# 780-00038_rev2_Pg1_SCH_Flex_Pwr_Sply.net
KiCad netlist of a schematic drawn in Altium Designer
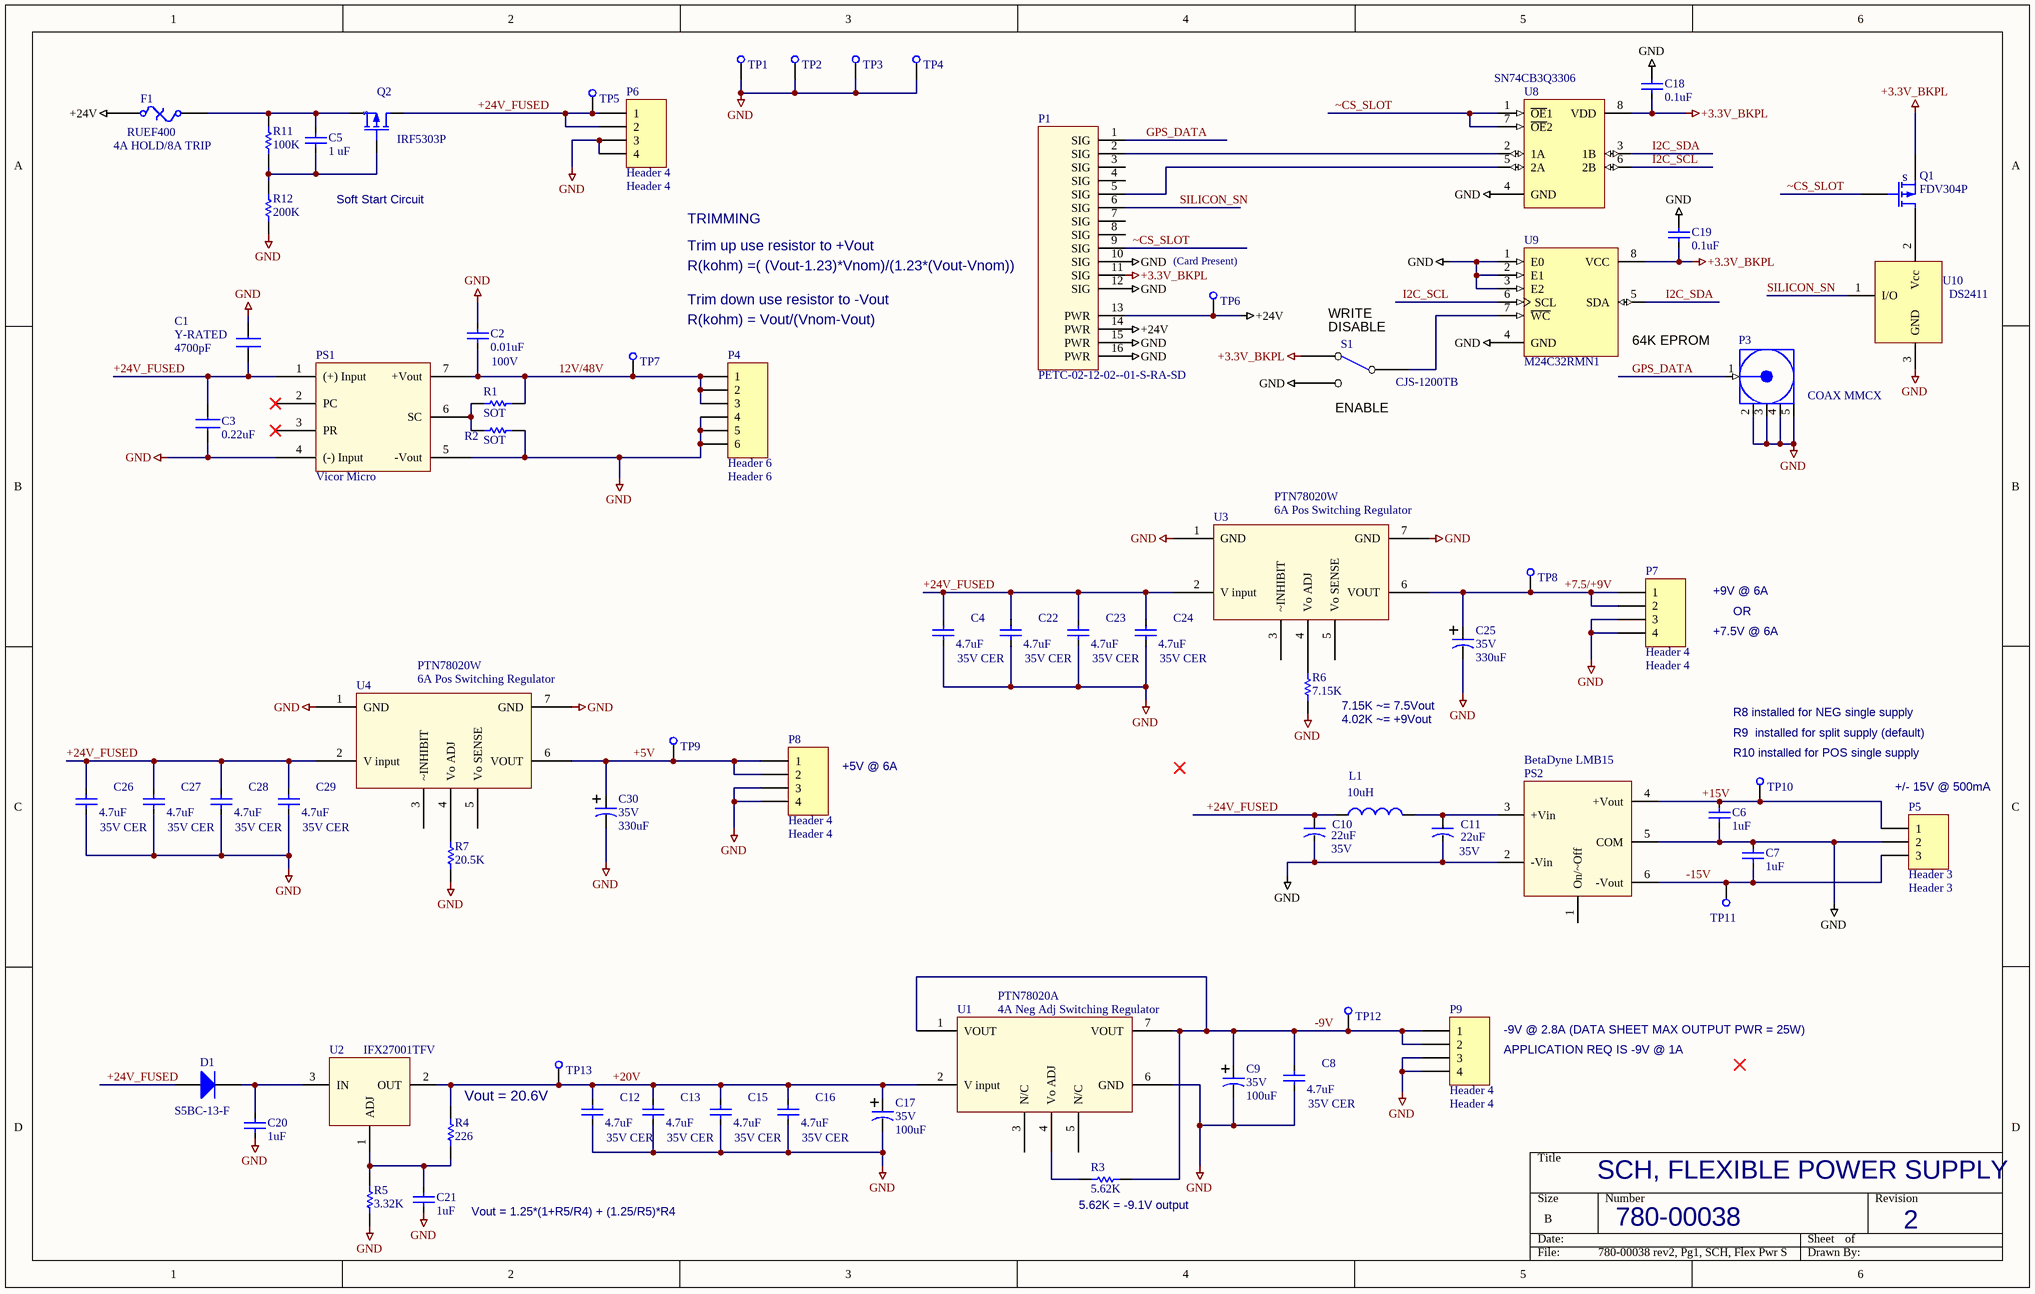
[diagram p0: 780-00038 rev2, Pg1, SCH, Flex Pwr Sply.SchDoc]

(export (version "E")
  (design (tool "Eeschema 10.0.6"))
  (components
    (comp (ref "C1")
      (value "Y-RATED")
      (footprint "1812")
      (fields (field (name "MANUFACTURER") "Murata") (field (name "ALTIUM_VALUE") "4700pF"))
      (libsource (lib "JON_1_Library") (part "CAP NP_DOUG"))
    )
    (comp (ref "C2")
      (value "100V")
      (footprint "SMD_0805")
      (description "Capacitor")
      (fields (field (name "MANUFACTURER") "Johanson") (field (name "ALTIUM_VALUE") "0.01uF"))
      (libsource (lib "Richs Schematic Components") (part "Cap SMD"))
    )
    (comp (ref "C3")
      (value "0.22uF")
      (footprint "1812")
      (fields (field (name "MANUFACTURER") "TDK"))
      (libsource (lib "JON_1_Library") (part "CAP NP_DOUG"))
    )
    (comp (ref "C4")
      (value "35V CER")
      (footprint "SMD_0805")
      (description "Capacitor")
      (fields (field (name "ALTIUM_VALUE") "4.7uF"))
      (libsource (lib "Richs Schematic Components") (part "Cap SMD"))
    )
    (comp (ref "C5")
      (value "1 uF")
      (footprint "SMD_0805")
      (description "Capacitor")
      (fields (field (name "Comment") "Cap SMD"))
      (libsource (lib "Richs Schematic Components") (part "Cap SMD"))
    )
    (comp (ref "C6")
      (value "1uF")
      (footprint "SMD_0805")
      (description "Capacitor")
      (fields (field (name "Comment") "Cap SMD"))
      (libsource (lib "Richs Schematic Components") (part "Cap SMD"))
    )
    (comp (ref "C7")
      (value "1uF")
      (footprint "SMD_0805")
      (description "Capacitor")
      (fields (field (name "Comment") "Cap SMD"))
      (libsource (lib "Richs Schematic Components") (part "Cap SMD"))
    )
    (comp (ref "C8")
      (value "35V CER")
      (footprint "SMD_0805")
      (description "Capacitor")
      (fields (field (name "ALTIUM_VALUE") "4.7uF"))
      (libsource (lib "Richs Schematic Components") (part "Cap SMD"))
    )
    (comp (ref "C9")
      (value "35V")
      (footprint "CAP, Thru Hole 8mm dia")
      (description "Radial Thru hole")
      (fields (field (name "ALTIUM_VALUE") "100uF"))
      (libsource (lib "Richs Schematic Components") (part "Cap Elec, 100 uF, 35V"))
    )
    (comp (ref "C10")
      (value "35V")
      (footprint "SMD_CAP_7343")
      (description "outline 6.0mm x 3.2mm")
      (fields (field (name "MANUFACTURER") "Kemet") (field (name "ALTIUM_VALUE") "22uF"))
      (libsource (lib "Richs Schematic Components") (part "Cap Tant 35V"))
    )
    (comp (ref "C11")
      (value "35V")
      (footprint "SMD_CAP_7343")
      (description "outline 6.0mm x 3.2mm")
      (fields (field (name "MANUFACTURER") "Kemet") (field (name "ALTIUM_VALUE") "22uF"))
      (libsource (lib "Richs Schematic Components") (part "Cap Tant 35V"))
    )
    (comp (ref "C12")
      (value "35V CER")
      (footprint "SMD_0805")
      (description "Capacitor")
      (fields (field (name "ALTIUM_VALUE") "4.7uF"))
      (libsource (lib "Richs Schematic Components") (part "Cap SMD"))
    )
    (comp (ref "C13")
      (value "35V CER")
      (footprint "SMD_0805")
      (description "Capacitor")
      (fields (field (name "ALTIUM_VALUE") "4.7uF"))
      (libsource (lib "Richs Schematic Components") (part "Cap SMD"))
    )
    (comp (ref "C15")
      (value "35V CER")
      (footprint "SMD_0805")
      (description "Capacitor")
      (fields (field (name "ALTIUM_VALUE") "4.7uF"))
      (libsource (lib "Richs Schematic Components") (part "Cap SMD"))
    )
    (comp (ref "C16")
      (value "35V CER")
      (footprint "SMD_0805")
      (description "Capacitor")
      (fields (field (name "ALTIUM_VALUE") "4.7uF"))
      (libsource (lib "Richs Schematic Components") (part "Cap SMD"))
    )
    (comp (ref "C17")
      (value "35V")
      (footprint "CAP, Thru Hole 8mm dia")
      (description "Radial Thru hole")
      (fields (field (name "ALTIUM_VALUE") "100uF"))
      (libsource (lib "Richs Schematic Components") (part "Cap Elec, 100 uF, 35V"))
    )
    (comp (ref "C18")
      (value "0.1uF")
      (footprint "SMD_0805")
      (description "Capacitor")
      (fields (field (name "MANUFACTURER") "AVX") (field (name "Comment") "Cap SMD"))
      (libsource (lib "Richs Schematic Components") (part "Cap SMD"))
    )
    (comp (ref "C19")
      (value "0.1uF")
      (footprint "SMD_0805")
      (description "Capacitor")
      (fields (field (name "MANUFACTURER") "AVX") (field (name "Comment") "Cap SMD"))
      (libsource (lib "Richs Schematic Components") (part "Cap SMD"))
    )
    (comp (ref "C20")
      (value "1uF")
      (footprint "SMD_0805")
      (description "Capacitor")
      (fields (field (name "Comment") "Cap SMD"))
      (libsource (lib "Richs Schematic Components") (part "Cap SMD"))
    )
    (comp (ref "C21")
      (value "1uF")
      (footprint "SMD_0805")
      (description "Capacitor")
      (fields (field (name "Comment") "Cap SMD"))
      (libsource (lib "Richs Schematic Components") (part "Cap SMD"))
    )
    (comp (ref "C22")
      (value "35V CER")
      (footprint "SMD_0805")
      (description "Capacitor")
      (fields (field (name "ALTIUM_VALUE") "4.7uF"))
      (libsource (lib "Richs Schematic Components") (part "Cap SMD"))
    )
    (comp (ref "C23")
      (value "35V CER")
      (footprint "SMD_0805")
      (description "Capacitor")
      (fields (field (name "ALTIUM_VALUE") "4.7uF"))
      (libsource (lib "Richs Schematic Components") (part "Cap SMD"))
    )
    (comp (ref "C24")
      (value "35V CER")
      (footprint "SMD_0805")
      (description "Capacitor")
      (fields (field (name "ALTIUM_VALUE") "4.7uF"))
      (libsource (lib "Richs Schematic Components") (part "Cap SMD"))
    )
    (comp (ref "C25")
      (value "35V")
      (footprint "CAP, Thru Hole 10mm dia")
      (description "Radial Thru hole")
      (fields (field (name "ALTIUM_VALUE") "330uF"))
      (libsource (lib "Richs Schematic Components") (part "Cap Elec, 330 uF, 35V"))
    )
    (comp (ref "C26")
      (value "35V CER")
      (footprint "SMD_0805")
      (description "Capacitor")
      (fields (field (name "ALTIUM_VALUE") "4.7uF"))
      (libsource (lib "Richs Schematic Components") (part "Cap SMD"))
    )
    (comp (ref "C27")
      (value "35V CER")
      (footprint "SMD_0805")
      (description "Capacitor")
      (fields (field (name "ALTIUM_VALUE") "4.7uF"))
      (libsource (lib "Richs Schematic Components") (part "Cap SMD"))
    )
    (comp (ref "C28")
      (value "35V CER")
      (footprint "SMD_0805")
      (description "Capacitor")
      (fields (field (name "ALTIUM_VALUE") "4.7uF"))
      (libsource (lib "Richs Schematic Components") (part "Cap SMD"))
    )
    (comp (ref "C29")
      (value "35V CER")
      (footprint "SMD_0805")
      (description "Capacitor")
      (fields (field (name "ALTIUM_VALUE") "4.7uF"))
      (libsource (lib "Richs Schematic Components") (part "Cap SMD"))
    )
    (comp (ref "C30")
      (value "35V")
      (footprint "CAP, Thru Hole 10mm dia")
      (description "Radial Thru hole")
      (fields (field (name "ALTIUM_VALUE") "330uF"))
      (libsource (lib "Richs Schematic Components") (part "Cap Elec, 330 uF, 35V"))
    )
    (comp (ref "D1")
      (value "S5BC-13-F")
      (footprint "SMC")
      (description "RECTIFIER GPP SMD 100V 5A SMC")
      (fields (field (name "MANUFACTURER") "Diodes Inc"))
      (libsource (lib "Miscellaneous Devices") (part "Diode"))
    )
    (comp (ref "F1")
      (value "RUEF400")
      (footprint "PolySwitch Radial 0.2")
      (description "PolySwitch RUE Series")
      (fields
        (field (name "MANUFACTURER") "Tyco Electronics")
        (field (name "ALTIUM_VALUE") "4A HOLD/8A TRIP")
      )
      (libsource (lib "Richs Schematic Components") (part "Fuse Thermal"))
    )
    (comp (ref "L1")
      (value "10uH")
      (footprint "Inductor TDC SLF")
      (description "Inductor")
      (fields (field (name "MANUFACTURER") "TDK") (field (name "Comment") "445-3869-1-ND"))
      (libsource (lib "Richs Schematic Components") (part "Inductor SMD 10uH 1.8A"))
    )
    (comp (ref "P1")
      (value "PETC-02-12-02--01-S-RA-SD")
      (footprint "PETC-02-12-02-01-RA")
      (description "SAMTEC, SIGNAL(12)+PWR(4)")
      (fields (field (name "MANUFACTURER") "SAMTEC"))
      (libsource (lib "Richs Schematic Components") (part "PETC-02-12-02--01-S-RA-SD"))
    )
    (comp (ref "P3")
      (value "COAX MMCX")
      (footprint "Miscellaneous Connectors:MMCX2.54-V5")
      (description "RF Coaxial PCB Connector, MMCX; Thru-Hole, Vertical Mount Plug,  50 Ohm Impedance")
      (fields (field (name "MANUFACTURER") "Emerson"))
      (libsource (lib "Richs Schematic Components") (part "COAX-M"))
    )
    (comp (ref "P4")
      (value "Header 6")
      (footprint "HDR1X6 for IDC")
      (description "Header, 6-Pin")
      (fields (field (name "ALTIUM_VALUE") "Header 6"))
      (libsource (lib "Richs Schematic Components") (part "Header 6"))
    )
    (comp (ref "P5")
      (value "Header 3")
      (footprint "HDR1X3 for IDC")
      (description "Header, 4-Pin")
      (fields (field (name "ALTIUM_VALUE") "Header 3"))
      (libsource (lib "Richs Schematic Components") (part "Header 3, MTA100"))
    )
    (comp (ref "P6")
      (value "Header 4")
      (footprint "HDR1X4 for IDC")
      (description "Header, 4-Pin")
      (fields (field (name "ALTIUM_VALUE") "Header 4"))
      (libsource (lib "Richs Schematic Components") (part "Header 4"))
    )
    (comp (ref "P7")
      (value "Header 4")
      (footprint "HDR1X4 for IDC")
      (description "Header, 4-Pin")
      (fields (field (name "ALTIUM_VALUE") "Header 4"))
      (libsource (lib "Richs Schematic Components") (part "Header 4"))
    )
    (comp (ref "P8")
      (value "Header 4")
      (footprint "HDR1X4 for IDC")
      (description "Header, 4-Pin")
      (fields (field (name "ALTIUM_VALUE") "Header 4"))
      (libsource (lib "Richs Schematic Components") (part "Header 4"))
    )
    (comp (ref "P9")
      (value "Header 4")
      (footprint "HDR1X4 for IDC")
      (description "Header, 4-Pin")
      (fields (field (name "ALTIUM_VALUE") "Header 4"))
      (libsource (lib "Richs Schematic Components") (part "Header 4"))
    )
    (comp (ref "PS1")
      (value "Vicor Micro")
      (footprint "Vicor Micro SurfMate")
      (libsource (lib "Richs Schematic Components") (part "Vicor Micro"))
    )
    (comp (ref "PS2")
      (value "BetaDyne LMB15")
      (footprint "BetaDyne LNB15, DC/DC")
      (description "DC/DC LMB15 15W, Dual Output")
      (libsource (lib "Richs Schematic Components") (part "BetaDyne LMB15"))
    )
    (comp (ref "Q1")
      (value "FDV304P")
      (footprint "SMD_SOT23_3")
      (description "P-MOSFET LOGIC LEVEL")
      (fields (field (name "MANUFACTURER") "Fairchild"))
      (libsource (lib "Richs Schematic Components") (part "FDV304P"))
    )
    (comp (ref "Q2")
      (value "IRF5303P")
      (footprint "TO-252(D-PAK)  PowerPAD")
      (description "P-Chan MOSFET")
      (fields (field (name "MANUFACTURER") "INT'l Rectifier"))
      (libsource (lib "Richs Schematic Components") (part "IRF5303P"))
    )
    (comp (ref "R1")
      (value "SOT")
      (footprint "SMD_0805")
      (description "Resistor 0805")
      (fields (field (name "MANUFACTURER") "Vishay/Dale") (field (name "Comment") "Res 0805"))
      (libsource (lib "Richs Schematic Components") (part "Res SMD"))
    )
    (comp (ref "R2")
      (value "SOT")
      (footprint "SMD_0805")
      (description "Resistor 0805")
      (fields (field (name "MANUFACTURER") "Vishay/Dale") (field (name "Comment") "Res 0805"))
      (libsource (lib "Richs Schematic Components") (part "Res SMD"))
    )
    (comp (ref "R3")
      (value "5.62K")
      (footprint "SMD_0805")
      (description "Resistor 0805")
      (fields (field (name "MANUFACTURER") "Vishay/Dale") (field (name "Comment") "Res 0805"))
      (libsource (lib "Richs Schematic Components") (part "Res SMD"))
    )
    (comp (ref "R4")
      (value "226")
      (footprint "SMD_0805")
      (description "Resistor 0805")
      (fields (field (name "MANUFACTURER") "Vishay/Dale") (field (name "Comment") "Res 0805"))
      (libsource (lib "Richs Schematic Components") (part "Res SMD"))
    )
    (comp (ref "R5")
      (value "3.32K")
      (footprint "SMD_0805")
      (description "Resistor 0805")
      (fields (field (name "MANUFACTURER") "Vishay/Dale") (field (name "Comment") "Res 0805"))
      (libsource (lib "Richs Schematic Components") (part "Res SMD"))
    )
    (comp (ref "R6")
      (value "7.15K")
      (footprint "SMD_0805")
      (description "Resistor 0805")
      (fields (field (name "MANUFACTURER") "Vishay/Dale") (field (name "Comment") "Res 0805"))
      (libsource (lib "Richs Schematic Components") (part "Res SMD"))
    )
    (comp (ref "R7")
      (value "20.5K")
      (footprint "SMD_0805")
      (description "Resistor 0805")
      (fields (field (name "MANUFACTURER") "Vishay/Dale") (field (name "Comment") "Res 0805"))
      (libsource (lib "Richs Schematic Components") (part "Res SMD"))
    )
    (comp (ref "R11")
      (value "100K")
      (footprint "SMD_0805")
      (description "Resistor 0805")
      (fields (field (name "MANUFACTURER") "Vishay/Dale") (field (name "Comment") "Res 0805"))
      (libsource (lib "Richs Schematic Components") (part "Res SMD"))
    )
    (comp (ref "R12")
      (value "200K")
      (footprint "SMD_0805")
      (description "Resistor 0805")
      (fields (field (name "MANUFACTURER") "Vishay/Dale") (field (name "Comment") "Res 0805"))
      (libsource (lib "Richs Schematic Components") (part "Res SMD"))
    )
    (comp (ref "S1")
      (value "CJS-1200TB")
      (footprint "CAS-120B")
      (fields (field (name "MANUFACTURER") "Copal Electronics"))
      (libsource (lib "JON_1_Library") (part "SW_SPDT_DOUG"))
    )
    (comp (ref "TP1")
      (value "Test point")
      (footprint "Protel 99SE BANKS PCB:PAD_80D_052H")
      (description "Test Point")
      (fields (field (name "MANUFACTURER") "Keystone"))
      (libsource (lib "Richs Schematic Components") (part "Test point"))
    )
    (comp (ref "TP2")
      (value "Test point")
      (footprint "Protel 99SE BANKS PCB:PAD_80D_052H")
      (description "Test Point")
      (fields (field (name "MANUFACTURER") "Keystone"))
      (libsource (lib "Richs Schematic Components") (part "Test point"))
    )
    (comp (ref "TP3")
      (value "Test point")
      (footprint "Protel 99SE BANKS PCB:PAD_80D_052H")
      (description "Test Point")
      (fields (field (name "MANUFACTURER") "Keystone"))
      (libsource (lib "Richs Schematic Components") (part "Test point"))
    )
    (comp (ref "TP4")
      (value "Test point")
      (footprint "Protel 99SE BANKS PCB:PAD_80D_052H")
      (description "Test Point")
      (fields (field (name "MANUFACTURER") "Keystone"))
      (libsource (lib "Richs Schematic Components") (part "Test point"))
    )
    (comp (ref "TP5")
      (value "Test point")
      (footprint "Protel 99SE BANKS PCB:PAD_80D_052H")
      (description "Test Point")
      (fields (field (name "MANUFACTURER") "Keystone"))
      (libsource (lib "Richs Schematic Components") (part "Test point"))
    )
    (comp (ref "TP6")
      (value "Test point")
      (footprint "Protel 99SE BANKS PCB:PAD_80D_052H")
      (description "Test Point")
      (fields (field (name "MANUFACTURER") "Keystone"))
      (libsource (lib "Richs Schematic Components") (part "Test point"))
    )
    (comp (ref "TP7")
      (value "Test point")
      (footprint "Protel 99SE BANKS PCB:PAD_80D_052H")
      (description "Test Point")
      (fields (field (name "MANUFACTURER") "Keystone"))
      (libsource (lib "Richs Schematic Components") (part "Test point"))
    )
    (comp (ref "TP8")
      (value "Test point")
      (footprint "Protel 99SE BANKS PCB:PAD_80D_052H")
      (description "Test Point")
      (fields (field (name "MANUFACTURER") "Keystone"))
      (libsource (lib "Richs Schematic Components") (part "Test point"))
    )
    (comp (ref "TP9")
      (value "Test point")
      (footprint "Protel 99SE BANKS PCB:PAD_80D_052H")
      (description "Test Point")
      (fields (field (name "MANUFACTURER") "Keystone"))
      (libsource (lib "Richs Schematic Components") (part "Test point"))
    )
    (comp (ref "TP10")
      (value "Test point")
      (footprint "Protel 99SE BANKS PCB:PAD_80D_052H")
      (description "Test Point")
      (fields (field (name "MANUFACTURER") "Keystone"))
      (libsource (lib "Richs Schematic Components") (part "Test point"))
    )
    (comp (ref "TP11")
      (value "Test point")
      (footprint "Protel 99SE BANKS PCB:PAD_80D_052H")
      (description "Test Point")
      (fields (field (name "MANUFACTURER") "Keystone"))
      (libsource (lib "Richs Schematic Components") (part "Test point"))
    )
    (comp (ref "TP12")
      (value "Test point")
      (footprint "Protel 99SE BANKS PCB:PAD_80D_052H")
      (description "Test Point")
      (fields (field (name "MANUFACTURER") "Keystone"))
      (libsource (lib "Richs Schematic Components") (part "Test point"))
    )
    (comp (ref "TP13")
      (value "Test point")
      (footprint "Protel 99SE BANKS PCB:PAD_80D_052H")
      (description "Test Point")
      (fields (field (name "MANUFACTURER") "Keystone"))
      (libsource (lib "Richs Schematic Components") (part "Test point"))
    )
    (comp (ref "U1")
      (value "4A Neg Adj Switching Regulator")
      (footprint "TEXAS Inst Switching Regulator")
      (description "Neg Adj Switching Regulator")
      (fields (field (name "ALTIUM_VALUE") "PTN78020A"))
      (libsource (lib "Richs Schematic Components") (part "PTN78020A"))
    )
    (comp (ref "U2")
      (value "IFX27001TFV")
      (footprint "TO-252(D-PAK)  PowerPAD")
      (description "IFX27001")
      (fields (field (name "MANUFACTURER") "Infineon") (field (name "Comment") "Voltage Reg, Adj"))
      (libsource (lib "Richs Schematic Components") (part "Voltage Reg, Adjustable"))
    )
    (comp (ref "U3")
      (value "6A Pos Switching Regulator")
      (footprint "TEXAS Inst Switching Regulator")
      (description "Pos Adj Switching Regulator")
      (fields (field (name "ALTIUM_VALUE") "PTN78020W"))
      (libsource (lib "Richs Schematic Components") (part "PTN78020W"))
    )
    (comp (ref "U4")
      (value "6A Pos Switching Regulator")
      (footprint "TEXAS Inst Switching Regulator")
      (description "Pos Adj Switching Regulator")
      (fields (field (name "ALTIUM_VALUE") "PTN78020W"))
      (libsource (lib "Richs Schematic Components") (part "PTN78020W"))
    )
    (comp (ref "U8")
      (value "SN74CB3Q3306")
      (footprint "PW008_N")
      (description "Dual FET Bus Switch")
      (fields (field (name "MANUFACTURER") "TI") (field (name "Comment") "SN74CBT3306PWLE"))
      (libsource (lib "TI Logic Switch") (part "SN74CBT3306PWLE"))
    )
    (comp (ref "U9")
      (value "M24C32RMN1")
      (footprint "SOP8_N")
      (description "32 Kbit Serial I²C Bus EEPROM")
      (libsource (lib "ST Memory EEPROM Serial") (part "M24C32RMN1"))
    )
    (comp (ref "U10")
      (value "DS2411")
      (footprint "SMD_SOT23_3")
      (description "Silicon Serial Number")
      (fields (field (name "MANUFACTURER") "Dallas"))
      (libsource (lib "Richs Schematic Components") (part "DS2411"))
    )
  )
  (nets
    (net (code "1") (name "+3.3V_BKPL") (class "Default")
      (node (ref "C18") (pin "1") (pinfunction "1_1") (pintype "passive"))
      (node (ref "C19") (pin "1") (pinfunction "1_1") (pintype "passive"))
      (node (ref "P1") (pin "11") (pinfunction "SIG_11") (pintype "passive"))
      (node (ref "Q1") (pin "2") (pinfunction "S_2") (pintype "passive"))
      (node (ref "S1") (pin "3") (pinfunction "NC_3") (pintype "passive"))
      (node (ref "U8") (pin "8") (pinfunction "VDD_8") (pintype "power_in"))
      (node (ref "U9") (pin "8") (pinfunction "VCC_8") (pintype "power_in"))
    )
    (net (code "2") (name "+24V") (class "Default")
      (node (ref "F1") (pin "1") (pinfunction "1_1") (pintype "passive"))
      (node (ref "P1") (pin "13") (pinfunction "PWR_13") (pintype "passive"))
      (node (ref "P1") (pin "14") (pinfunction "PWR_14") (pintype "passive"))
      (node (ref "TP6") (pin "1") (pinfunction "TP_1") (pintype "passive"))
    )
    (net (code "3") (name "/+5V") (class "Default")
      (node (ref "C30") (pin "1") (pinfunction "1_1") (pintype "passive"))
      (node (ref "P8") (pin "1") (pinfunction "1_1") (pintype "passive"))
      (node (ref "P8") (pin "2") (pinfunction "2_2") (pintype "passive"))
      (node (ref "TP9") (pin "1") (pinfunction "TP_1") (pintype "passive"))
      (node (ref "U4") (pin "6") (pinfunction "VOUT_6") (pintype "passive"))
    )
    (net (code "4") (name "/+7.5{slash}+9V") (class "Default")
      (node (ref "C25") (pin "1") (pinfunction "1_1") (pintype "passive"))
      (node (ref "P7") (pin "1") (pinfunction "1_1") (pintype "passive"))
      (node (ref "P7") (pin "2") (pinfunction "2_2") (pintype "passive"))
      (node (ref "TP8") (pin "1") (pinfunction "TP_1") (pintype "passive"))
      (node (ref "U3") (pin "6") (pinfunction "VOUT_6") (pintype "passive"))
    )
    (net (code "5") (name "/+15V") (class "Default")
      (node (ref "C6") (pin "2") (pinfunction "2_2") (pintype "passive"))
      (node (ref "P5") (pin "1") (pinfunction "1_1") (pintype "passive"))
      (node (ref "PS2") (pin "4") (pinfunction "+Vout_4") (pintype "passive"))
      (node (ref "TP10") (pin "1") (pinfunction "TP_1") (pintype "passive"))
    )
    (net (code "6") (name "/+20V") (class "Default")
      (node (ref "C12") (pin "2") (pinfunction "2_2") (pintype "passive"))
      (node (ref "C13") (pin "2") (pinfunction "2_2") (pintype "passive"))
      (node (ref "C15") (pin "2") (pinfunction "2_2") (pintype "passive"))
      (node (ref "C16") (pin "2") (pinfunction "2_2") (pintype "passive"))
      (node (ref "C17") (pin "1") (pinfunction "1_1") (pintype "passive"))
      (node (ref "R4") (pin "2") (pinfunction "2_2") (pintype "passive"))
      (node (ref "TP13") (pin "1") (pinfunction "TP_1") (pintype "passive"))
      (node (ref "U1") (pin "2") (pinfunction "V_input_2") (pintype "passive"))
      (node (ref "U2") (pin "2") (pinfunction "OUT_2") (pintype "passive"))
    )
    (net (code "7") (name "/+24V_FUSED") (class "Default")
      (node (ref "C1") (pin "2") (pinfunction "2_2") (pintype "passive"))
      (node (ref "C10") (pin "pos") (pinfunction "1_pos") (pintype "passive"))
      (node (ref "C22") (pin "2") (pinfunction "2_2") (pintype "passive"))
      (node (ref "C23") (pin "2") (pinfunction "2_2") (pintype "passive"))
      (node (ref "C24") (pin "2") (pinfunction "2_2") (pintype "passive"))
      (node (ref "C26") (pin "2") (pinfunction "2_2") (pintype "passive"))
      (node (ref "C27") (pin "2") (pinfunction "2_2") (pintype "passive"))
      (node (ref "C28") (pin "2") (pinfunction "2_2") (pintype "passive"))
      (node (ref "C29") (pin "2") (pinfunction "2_2") (pintype "passive"))
      (node (ref "C3") (pin "2") (pinfunction "2_2") (pintype "passive"))
      (node (ref "C4") (pin "2") (pinfunction "2_2") (pintype "passive"))
      (node (ref "D1") (pin "1") (pinfunction "A_1") (pintype "passive"))
      (node (ref "L1") (pin "1") (pinfunction "1_1") (pintype "passive"))
      (node (ref "P6") (pin "1") (pinfunction "1_1") (pintype "passive"))
      (node (ref "P6") (pin "2") (pinfunction "2_2") (pintype "passive"))
      (node (ref "PS1") (pin "1") (pinfunction "(+)_Input_1") (pintype "passive"))
      (node (ref "Q2") (pin "2") (pinfunction "D_2") (pintype "passive"))
      (node (ref "TP5") (pin "1") (pinfunction "TP_1") (pintype "passive"))
      (node (ref "U3") (pin "2") (pinfunction "V_input_2") (pintype "passive"))
      (node (ref "U4") (pin "2") (pinfunction "V_input_2") (pintype "passive"))
    )
    (net (code "8") (name "/-9V") (class "Default")
      (node (ref "C8") (pin "2") (pinfunction "2_2") (pintype "passive"))
      (node (ref "C9") (pin "1") (pinfunction "1_1") (pintype "passive"))
      (node (ref "P9") (pin "1") (pinfunction "1_1") (pintype "passive"))
      (node (ref "P9") (pin "2") (pinfunction "2_2") (pintype "passive"))
      (node (ref "R3") (pin "2") (pinfunction "2_2") (pintype "passive"))
      (node (ref "TP12") (pin "1") (pinfunction "TP_1") (pintype "passive"))
      (node (ref "U1") (pin "1") (pinfunction "VOUT_1") (pintype "passive"))
      (node (ref "U1") (pin "7") (pinfunction "VOUT_7") (pintype "passive"))
    )
    (net (code "9") (name "/-15V") (class "Default")
      (node (ref "C7") (pin "1") (pinfunction "1_1") (pintype "passive"))
      (node (ref "P5") (pin "3") (pinfunction "3_3") (pintype "passive"))
      (node (ref "PS2") (pin "6") (pinfunction "-Vout_6") (pintype "passive"))
      (node (ref "TP11") (pin "1") (pinfunction "TP_1") (pintype "passive"))
    )
    (net (code "10") (name "/12V{slash}48V") (class "Default")
      (node (ref "C2") (pin "1") (pinfunction "1_1") (pintype "passive"))
      (node (ref "P4") (pin "1") (pinfunction "1_1") (pintype "passive"))
      (node (ref "P4") (pin "2") (pinfunction "2_2") (pintype "passive"))
      (node (ref "P4") (pin "3") (pinfunction "3_3") (pintype "passive"))
      (node (ref "PS1") (pin "7") (pinfunction "+Vout_7") (pintype "passive"))
      (node (ref "R1") (pin "2") (pinfunction "2_2") (pintype "passive"))
      (node (ref "TP7") (pin "1") (pinfunction "TP_1") (pintype "passive"))
    )
    (net (code "11") (name "/GPS_DATA") (class "Default")
      (node (ref "P1") (pin "1") (pinfunction "SIG_1") (pintype "passive"))
      (node (ref "P3") (pin "1") (pinfunction "Signal_1") (pintype "input"))
    )
    (net (code "12") (name "/I2C_SCL") (class "Default")
      (node (ref "U8") (pin "6") (pinfunction "2B_6") (pintype "bidirectional"))
      (node (ref "U9") (pin "6") (pinfunction "SCL_6") (pintype "input"))
    )
    (net (code "13") (name "/I2C_SDA") (class "Default")
      (node (ref "U8") (pin "3") (pinfunction "1B_3") (pintype "bidirectional"))
      (node (ref "U9") (pin "5") (pinfunction "SDA_5") (pintype "bidirectional"))
    )
    (net (code "14") (name "/SILICON_SN") (class "Default")
      (node (ref "P1") (pin "6") (pinfunction "SIG_6") (pintype "passive"))
      (node (ref "U10") (pin "1") (pinfunction "I/O_1") (pintype "passive"))
    )
    (net (code "15") (name "/~CS_SLOT") (class "Default")
      (node (ref "P1") (pin "9") (pinfunction "SIG_9") (pintype "passive"))
      (node (ref "Q1") (pin "1") (pinfunction "G_1") (pintype "passive"))
      (node (ref "U8") (pin "1") (pinfunction "~{OE}1_1") (pintype "input"))
      (node (ref "U8") (pin "7") (pinfunction "~{OE}2_7") (pintype "input"))
    )
    (net (code "16") (name "GND") (class "Default")
      (node (ref "C1") (pin "1") (pinfunction "1_1") (pintype "passive"))
      (node (ref "C10") (pin "neg") (pinfunction "2_neg") (pintype "passive"))
      (node (ref "C11") (pin "neg") (pinfunction "2_neg") (pintype "passive"))
      (node (ref "C12") (pin "1") (pinfunction "1_1") (pintype "passive"))
      (node (ref "C13") (pin "1") (pinfunction "1_1") (pintype "passive"))
      (node (ref "C15") (pin "1") (pinfunction "1_1") (pintype "passive"))
      (node (ref "C16") (pin "1") (pinfunction "1_1") (pintype "passive"))
      (node (ref "C17") (pin "2") (pinfunction "2_2") (pintype "passive"))
      (node (ref "C18") (pin "2") (pinfunction "2_2") (pintype "passive"))
      (node (ref "C19") (pin "2") (pinfunction "2_2") (pintype "passive"))
      (node (ref "C2") (pin "2") (pinfunction "2_2") (pintype "passive"))
      (node (ref "C20") (pin "1") (pinfunction "1_1") (pintype "passive"))
      (node (ref "C21") (pin "1") (pinfunction "1_1") (pintype "passive"))
      (node (ref "C22") (pin "1") (pinfunction "1_1") (pintype "passive"))
      (node (ref "C23") (pin "1") (pinfunction "1_1") (pintype "passive"))
      (node (ref "C24") (pin "1") (pinfunction "1_1") (pintype "passive"))
      (node (ref "C25") (pin "2") (pinfunction "2_2") (pintype "passive"))
      (node (ref "C26") (pin "1") (pinfunction "1_1") (pintype "passive"))
      (node (ref "C27") (pin "1") (pinfunction "1_1") (pintype "passive"))
      (node (ref "C28") (pin "1") (pinfunction "1_1") (pintype "passive"))
      (node (ref "C29") (pin "1") (pinfunction "1_1") (pintype "passive"))
      (node (ref "C3") (pin "1") (pinfunction "1_1") (pintype "passive"))
      (node (ref "C30") (pin "2") (pinfunction "2_2") (pintype "passive"))
      (node (ref "C4") (pin "1") (pinfunction "1_1") (pintype "passive"))
      (node (ref "C6") (pin "1") (pinfunction "1_1") (pintype "passive"))
      (node (ref "C7") (pin "2") (pinfunction "2_2") (pintype "passive"))
      (node (ref "C8") (pin "1") (pinfunction "1_1") (pintype "passive"))
      (node (ref "C9") (pin "2") (pinfunction "2_2") (pintype "passive"))
      (node (ref "P1") (pin "10") (pinfunction "SIG_10") (pintype "passive"))
      (node (ref "P1") (pin "12") (pinfunction "SIG_12") (pintype "passive"))
      (node (ref "P1") (pin "15") (pinfunction "PWR_15") (pintype "passive"))
      (node (ref "P1") (pin "16") (pinfunction "PWR_16") (pintype "passive"))
      (node (ref "P3") (pin "2") (pinfunction "GND_2") (pintype "power_in"))
      (node (ref "P3") (pin "3") (pinfunction "GND_3") (pintype "power_in"))
      (node (ref "P3") (pin "4") (pinfunction "GND_4") (pintype "power_in"))
      (node (ref "P3") (pin "5") (pinfunction "GND_5") (pintype "power_in"))
      (node (ref "P4") (pin "4") (pinfunction "4_4") (pintype "passive"))
      (node (ref "P4") (pin "5") (pinfunction "5_5") (pintype "passive"))
      (node (ref "P4") (pin "6") (pinfunction "6_6") (pintype "passive"))
      (node (ref "P5") (pin "2") (pinfunction "2_2") (pintype "passive"))
      (node (ref "P6") (pin "3") (pinfunction "3_3") (pintype "passive"))
      (node (ref "P6") (pin "4") (pinfunction "4_4") (pintype "passive"))
      (node (ref "P7") (pin "3") (pinfunction "3_3") (pintype "passive"))
      (node (ref "P7") (pin "4") (pinfunction "4_4") (pintype "passive"))
      (node (ref "P8") (pin "3") (pinfunction "3_3") (pintype "passive"))
      (node (ref "P8") (pin "4") (pinfunction "4_4") (pintype "passive"))
      (node (ref "P9") (pin "3") (pinfunction "3_3") (pintype "passive"))
      (node (ref "P9") (pin "4") (pinfunction "4_4") (pintype "passive"))
      (node (ref "PS1") (pin "4") (pinfunction "(-)_Input_4") (pintype "passive"))
      (node (ref "PS1") (pin "5") (pinfunction "-Vout_5") (pintype "passive"))
      (node (ref "PS2") (pin "2") (pinfunction "-Vin_2") (pintype "passive"))
      (node (ref "PS2") (pin "5") (pinfunction "COM_5") (pintype "passive"))
      (node (ref "R12") (pin "1") (pinfunction "1_1") (pintype "passive"))
      (node (ref "R2") (pin "2") (pinfunction "2_2") (pintype "passive"))
      (node (ref "R5") (pin "1") (pinfunction "1_1") (pintype "passive"))
      (node (ref "R6") (pin "1") (pinfunction "1_1") (pintype "passive"))
      (node (ref "R7") (pin "1") (pinfunction "1_1") (pintype "passive"))
      (node (ref "S1") (pin "1") (pinfunction "NO_1") (pintype "passive"))
      (node (ref "TP1") (pin "1") (pinfunction "TP_1") (pintype "passive"))
      (node (ref "TP2") (pin "1") (pinfunction "TP_1") (pintype "passive"))
      (node (ref "TP3") (pin "1") (pinfunction "TP_1") (pintype "passive"))
      (node (ref "TP4") (pin "1") (pinfunction "TP_1") (pintype "passive"))
      (node (ref "U1") (pin "6") (pinfunction "GND_6") (pintype "passive"))
      (node (ref "U10") (pin "3") (pinfunction "GND_3") (pintype "passive"))
      (node (ref "U3") (pin "1") (pinfunction "GND_1") (pintype "passive"))
      (node (ref "U3") (pin "7") (pinfunction "GND_7") (pintype "passive"))
      (node (ref "U4") (pin "1") (pinfunction "GND_1") (pintype "passive"))
      (node (ref "U4") (pin "7") (pinfunction "GND_7") (pintype "passive"))
      (node (ref "U8") (pin "4") (pinfunction "GND_4") (pintype "power_in"))
      (node (ref "U9") (pin "1") (pinfunction "E0_1") (pintype "input"))
      (node (ref "U9") (pin "2") (pinfunction "E1_2") (pintype "input"))
      (node (ref "U9") (pin "3") (pinfunction "E2_3") (pintype "input"))
      (node (ref "U9") (pin "4") (pinfunction "GND_4") (pintype "power_in"))
    )
    (net (code "17") (name "Net-(C11-1)") (class "Default")
      (node (ref "C11") (pin "pos") (pinfunction "1_pos") (pintype "passive"))
      (node (ref "L1") (pin "2") (pinfunction "2_2") (pintype "passive"))
      (node (ref "PS2") (pin "3") (pinfunction "+Vin_3") (pintype "passive"))
    )
    (net (code "18") (name "Net-(D1-K)") (class "Default")
      (node (ref "C20") (pin "2") (pinfunction "2_2") (pintype "passive"))
      (node (ref "D1") (pin "2") (pinfunction "K_2") (pintype "passive"))
      (node (ref "U2") (pin "3") (pinfunction "IN_3") (pintype "passive"))
    )
    (net (code "19") (name "Net-(PS1-SC)") (class "Default")
      (node (ref "PS1") (pin "6") (pinfunction "SC_6") (pintype "passive"))
      (node (ref "R1") (pin "1") (pinfunction "1_1") (pintype "passive"))
      (node (ref "R2") (pin "1") (pinfunction "1_1") (pintype "passive"))
    )
    (net (code "20") (name "Net-(Q1-D)") (class "Default")
      (node (ref "Q1") (pin "3") (pinfunction "D_3") (pintype "passive"))
      (node (ref "U10") (pin "2") (pinfunction "Vcc_2") (pintype "passive"))
    )
    (net (code "21") (name "Net-(Q2-G)") (class "Default")
      (node (ref "C5") (pin "1") (pinfunction "1_1") (pintype "passive"))
      (node (ref "Q2") (pin "1") (pinfunction "G_1") (pintype "passive"))
      (node (ref "R11") (pin "1") (pinfunction "1_1") (pintype "passive"))
      (node (ref "R12") (pin "2") (pinfunction "2_2") (pintype "passive"))
    )
    (net (code "22") (name "Net-(Q2-S)") (class "Default")
      (node (ref "C5") (pin "2") (pinfunction "2_2") (pintype "passive"))
      (node (ref "F1") (pin "2") (pinfunction "2_2") (pintype "passive"))
      (node (ref "Q2") (pin "3") (pinfunction "S_3") (pintype "passive"))
      (node (ref "R11") (pin "2") (pinfunction "2_2") (pintype "passive"))
    )
    (net (code "23") (name "Net-(S1-COM)") (class "Default")
      (node (ref "S1") (pin "2") (pinfunction "COM_2") (pintype "passive"))
      (node (ref "U9") (pin "7") (pinfunction "~{WC}_7") (pintype "input"))
    )
    (net (code "24") (name "Net-(U1-Vo_ADJ)") (class "Default")
      (node (ref "R3") (pin "1") (pinfunction "1_1") (pintype "passive"))
      (node (ref "U1") (pin "4") (pinfunction "Vo_ADJ_4") (pintype "passive"))
    )
    (net (code "25") (name "Net-(U2-ADJ)") (class "Default")
      (node (ref "C21") (pin "2") (pinfunction "2_2") (pintype "passive"))
      (node (ref "R4") (pin "1") (pinfunction "1_1") (pintype "passive"))
      (node (ref "R5") (pin "2") (pinfunction "2_2") (pintype "passive"))
      (node (ref "U2") (pin "1") (pinfunction "ADJ_1") (pintype "passive"))
    )
    (net (code "26") (name "Net-(U3-Vo_ADJ)") (class "Default")
      (node (ref "R6") (pin "2") (pinfunction "2_2") (pintype "passive"))
      (node (ref "U3") (pin "4") (pinfunction "Vo_ADJ_4") (pintype "passive"))
    )
    (net (code "27") (name "Net-(U4-Vo_ADJ)") (class "Default")
      (node (ref "R7") (pin "2") (pinfunction "2_2") (pintype "passive"))
      (node (ref "U4") (pin "4") (pinfunction "Vo_ADJ_4") (pintype "passive"))
    )
    (net (code "28") (name "Net-(U8-1A)") (class "Default")
      (node (ref "P1") (pin "2") (pinfunction "SIG_2") (pintype "passive"))
      (node (ref "U8") (pin "2") (pinfunction "1A_2") (pintype "bidirectional"))
    )
    (net (code "29") (name "Net-(U8-2A)") (class "Default")
      (node (ref "P1") (pin "5") (pinfunction "SIG_5") (pintype "passive"))
      (node (ref "U8") (pin "5") (pinfunction "2A_5") (pintype "bidirectional"))
    )
    (net (code "30") (name "unconnected-(P1-SIG-Pad3)") (class "Default")
      (node (ref "P1") (pin "3") (pinfunction "SIG_3") (pintype "passive"))
    )
    (net (code "31") (name "unconnected-(P1-SIG-Pad4)") (class "Default")
      (node (ref "P1") (pin "4") (pinfunction "SIG_4") (pintype "passive"))
    )
    (net (code "32") (name "unconnected-(P1-SIG-Pad7)") (class "Default")
      (node (ref "P1") (pin "7") (pinfunction "SIG_7") (pintype "passive"))
    )
    (net (code "33") (name "unconnected-(P1-SIG-Pad8)") (class "Default")
      (node (ref "P1") (pin "8") (pinfunction "SIG_8") (pintype "passive"))
    )
    (net (code "34") (name "unconnected-(PS1-PC-Pad2)") (class "Default")
      (node (ref "PS1") (pin "2") (pinfunction "PC_2") (pintype "passive+no_connect"))
    )
    (net (code "35") (name "unconnected-(PS1-PR-Pad3)") (class "Default")
      (node (ref "PS1") (pin "3") (pinfunction "PR_3") (pintype "passive+no_connect"))
    )
    (net (code "36") (name "unconnected-(PS2-On{slash}~Off-Pad1)") (class "Default")
      (node (ref "PS2") (pin "1") (pinfunction "On/~Off_1") (pintype "passive"))
    )
    (net (code "37") (name "unconnected-(U1-N{slash}C-Pad3)") (class "Default")
      (node (ref "U1") (pin "3") (pinfunction "N/C_3") (pintype "passive"))
    )
    (net (code "38") (name "unconnected-(U1-N{slash}C-Pad5)") (class "Default")
      (node (ref "U1") (pin "5") (pinfunction "N/C_5") (pintype "passive"))
    )
    (net (code "39") (name "unconnected-(U3-Vo_SENSE-Pad5)") (class "Default")
      (node (ref "U3") (pin "5") (pinfunction "Vo_SENSE_5") (pintype "passive"))
    )
    (net (code "40") (name "unconnected-(U3-~INHIBIT-Pad3)") (class "Default")
      (node (ref "U3") (pin "3") (pinfunction "~INHIBIT_3") (pintype "passive"))
    )
    (net (code "41") (name "unconnected-(U4-Vo_SENSE-Pad5)") (class "Default")
      (node (ref "U4") (pin "5") (pinfunction "Vo_SENSE_5") (pintype "passive"))
    )
    (net (code "42") (name "unconnected-(U4-~INHIBIT-Pad3)") (class "Default")
      (node (ref "U4") (pin "3") (pinfunction "~INHIBIT_3") (pintype "passive"))
    )
  )
)
